# LuMini_1Inch.net
KiCad netlist of a schematic drawn in EAGLE
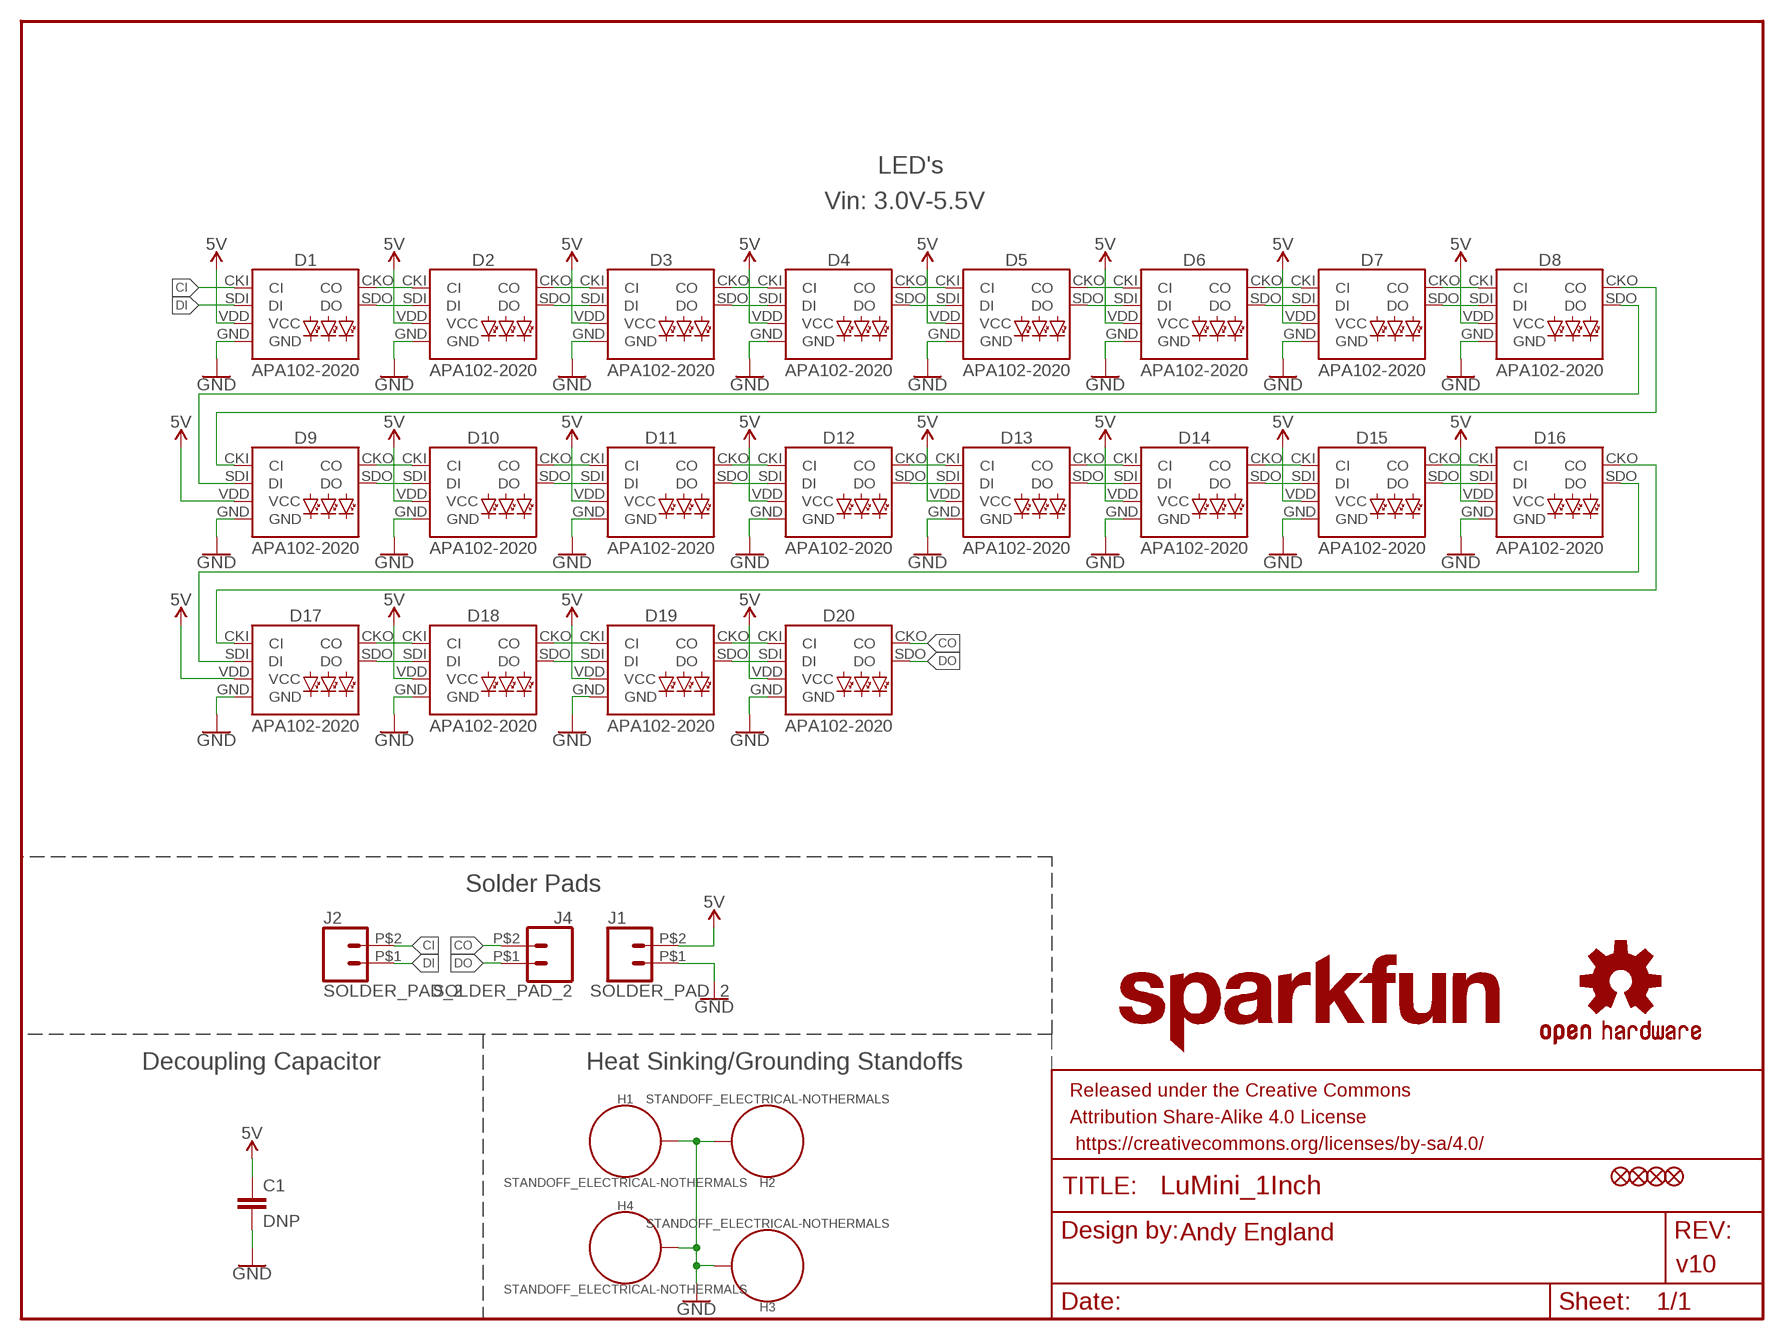
[diagram p0: schematic, sheet 1]

(export (version "E")
  (design (tool "Eeschema 10.0.6"))
  (components
    (comp (ref "C1")
      (value "DNP")
      (footprint "eagle-import:0603")
      (libsource (lib "eagle-import") (part "4.7UF-0603-6.3V-(10%)"))
    )
    (comp (ref "D1")
      (value "APA102-2020")
      (footprint "eagle-import:APA102-2020")
      (libsource (lib "eagle-import") (part "APA102-2020"))
    )
    (comp (ref "D2")
      (value "APA102-2020")
      (footprint "eagle-import:APA102-2020")
      (libsource (lib "eagle-import") (part "APA102-2020"))
    )
    (comp (ref "D3")
      (value "APA102-2020")
      (footprint "eagle-import:APA102-2020")
      (libsource (lib "eagle-import") (part "APA102-2020"))
    )
    (comp (ref "D4")
      (value "APA102-2020")
      (footprint "eagle-import:APA102-2020")
      (libsource (lib "eagle-import") (part "APA102-2020"))
    )
    (comp (ref "D5")
      (value "APA102-2020")
      (footprint "eagle-import:APA102-2020")
      (libsource (lib "eagle-import") (part "APA102-2020"))
    )
    (comp (ref "D6")
      (value "APA102-2020")
      (footprint "eagle-import:APA102-2020")
      (libsource (lib "eagle-import") (part "APA102-2020"))
    )
    (comp (ref "D7")
      (value "APA102-2020")
      (footprint "eagle-import:APA102-2020")
      (libsource (lib "eagle-import") (part "APA102-2020"))
    )
    (comp (ref "D8")
      (value "APA102-2020")
      (footprint "eagle-import:APA102-2020")
      (libsource (lib "eagle-import") (part "APA102-2020"))
    )
    (comp (ref "D9")
      (value "APA102-2020")
      (footprint "eagle-import:APA102-2020")
      (libsource (lib "eagle-import") (part "APA102-2020"))
    )
    (comp (ref "D10")
      (value "APA102-2020")
      (footprint "eagle-import:APA102-2020")
      (libsource (lib "eagle-import") (part "APA102-2020"))
    )
    (comp (ref "D11")
      (value "APA102-2020")
      (footprint "eagle-import:APA102-2020")
      (libsource (lib "eagle-import") (part "APA102-2020"))
    )
    (comp (ref "D12")
      (value "APA102-2020")
      (footprint "eagle-import:APA102-2020")
      (libsource (lib "eagle-import") (part "APA102-2020"))
    )
    (comp (ref "D13")
      (value "APA102-2020")
      (footprint "eagle-import:APA102-2020")
      (libsource (lib "eagle-import") (part "APA102-2020"))
    )
    (comp (ref "D14")
      (value "APA102-2020")
      (footprint "eagle-import:APA102-2020")
      (libsource (lib "eagle-import") (part "APA102-2020"))
    )
    (comp (ref "D15")
      (value "APA102-2020")
      (footprint "eagle-import:APA102-2020")
      (libsource (lib "eagle-import") (part "APA102-2020"))
    )
    (comp (ref "D16")
      (value "APA102-2020")
      (footprint "eagle-import:APA102-2020")
      (libsource (lib "eagle-import") (part "APA102-2020"))
    )
    (comp (ref "D17")
      (value "APA102-2020")
      (footprint "eagle-import:APA102-2020")
      (libsource (lib "eagle-import") (part "APA102-2020"))
    )
    (comp (ref "D18")
      (value "APA102-2020")
      (footprint "eagle-import:APA102-2020")
      (libsource (lib "eagle-import") (part "APA102-2020"))
    )
    (comp (ref "D19")
      (value "APA102-2020")
      (footprint "eagle-import:APA102-2020")
      (libsource (lib "eagle-import") (part "APA102-2020"))
    )
    (comp (ref "D20")
      (value "APA102-2020")
      (footprint "eagle-import:APA102-2020")
      (libsource (lib "eagle-import") (part "APA102-2020"))
    )
    (comp (ref "FD1")
      (value "FIDUCIALUFIDUCIAL")
      (footprint "eagle-import:FIDUCIAL-MICRO")
      (libsource (lib "eagle-import") (part "FIDUCIALUFIDUCIAL"))
    )
    (comp (ref "FD2")
      (value "FIDUCIALUFIDUCIAL")
      (footprint "eagle-import:FIDUCIAL-MICRO")
      (libsource (lib "eagle-import") (part "FIDUCIALUFIDUCIAL"))
    )
    (comp (ref "FD3")
      (value "FIDUCIALUFIDUCIAL")
      (footprint "eagle-import:FIDUCIAL-MICRO")
      (libsource (lib "eagle-import") (part "FIDUCIALUFIDUCIAL"))
    )
    (comp (ref "FD4")
      (value "FIDUCIALUFIDUCIAL")
      (footprint "eagle-import:FIDUCIAL-MICRO")
      (libsource (lib "eagle-import") (part "FIDUCIALUFIDUCIAL"))
    )
    (comp (ref "FRAME1")
      (value "FRAME-LETTER")
      (footprint "eagle-import:CREATIVE_COMMONS")
      (libsource (lib "eagle-import") (part "FRAME-LETTER"))
    )
    (comp (ref "H1")
      (value "STANDOFF_ELECTRICAL-NOTHERMALS")
      (footprint "eagle-import:STANDOFF-ELECTRICAL-NOTHERMALS")
      (libsource (lib "eagle-import") (part "STANDOFF_ELECTRICAL-NOTHERMALS"))
    )
    (comp (ref "H2")
      (value "STANDOFF_ELECTRICAL-NOTHERMALS")
      (footprint "eagle-import:STANDOFF-ELECTRICAL-NOTHERMALS")
      (libsource (lib "eagle-import") (part "STANDOFF_ELECTRICAL-NOTHERMALS"))
    )
    (comp (ref "H3")
      (value "STANDOFF_ELECTRICAL-NOTHERMALS")
      (footprint "eagle-import:STANDOFF-ELECTRICAL-NOTHERMALS")
      (libsource (lib "eagle-import") (part "STANDOFF_ELECTRICAL-NOTHERMALS"))
    )
    (comp (ref "H4")
      (value "STANDOFF_ELECTRICAL-NOTHERMALS")
      (footprint "eagle-import:STANDOFF-ELECTRICAL-NOTHERMALS")
      (libsource (lib "eagle-import") (part "STANDOFF_ELECTRICAL-NOTHERMALS"))
    )
    (comp (ref "J1")
      (value "SOLDER_PAD_2")
      (footprint "eagle-import:SOLDER_PAD_2")
      (libsource (lib "eagle-import") (part "SOLDER_PAD_2"))
    )
    (comp (ref "J2")
      (value "SOLDER_PAD_2")
      (footprint "eagle-import:SOLDER_PAD_2")
      (libsource (lib "eagle-import") (part "SOLDER_PAD_2"))
    )
    (comp (ref "J4")
      (value "SOLDER_PAD_2")
      (footprint "eagle-import:SOLDER_PAD_2")
      (libsource (lib "eagle-import") (part "SOLDER_PAD_2"))
    )
    (comp (ref "LOGO1")
      (value "SFE_LOGO_NAME.1_INCH")
      (footprint "eagle-import:SFE_LOGO_NAME_.1")
      (libsource (lib "eagle-import") (part "SFE_LOGO_NAME.1_INCH"))
    )
    (comp (ref "LOGO2")
      (value "OSHW-LOGOS")
      (footprint "eagle-import:OSHW-LOGO-S")
      (libsource (lib "eagle-import") (part "OSHW-LOGOS"))
    )
  )
  (nets
    (net (code "1") (name "5V") (class "Default")
      (node (ref "C1") (pin "1") (pinfunction "1_1") (pintype "passive"))
      (node (ref "D1") (pin "VDD") (pinfunction "VCC_VDD") (pintype "bidirectional"))
      (node (ref "D10") (pin "VDD") (pinfunction "VCC_VDD") (pintype "bidirectional"))
      (node (ref "D11") (pin "VDD") (pinfunction "VCC_VDD") (pintype "bidirectional"))
      (node (ref "D12") (pin "VDD") (pinfunction "VCC_VDD") (pintype "bidirectional"))
      (node (ref "D13") (pin "VDD") (pinfunction "VCC_VDD") (pintype "bidirectional"))
      (node (ref "D14") (pin "VDD") (pinfunction "VCC_VDD") (pintype "bidirectional"))
      (node (ref "D15") (pin "VDD") (pinfunction "VCC_VDD") (pintype "bidirectional"))
      (node (ref "D16") (pin "VDD") (pinfunction "VCC_VDD") (pintype "bidirectional"))
      (node (ref "D17") (pin "VDD") (pinfunction "VCC_VDD") (pintype "bidirectional"))
      (node (ref "D18") (pin "VDD") (pinfunction "VCC_VDD") (pintype "bidirectional"))
      (node (ref "D19") (pin "VDD") (pinfunction "VCC_VDD") (pintype "bidirectional"))
      (node (ref "D2") (pin "VDD") (pinfunction "VCC_VDD") (pintype "bidirectional"))
      (node (ref "D20") (pin "VDD") (pinfunction "VCC_VDD") (pintype "bidirectional"))
      (node (ref "D3") (pin "VDD") (pinfunction "VCC_VDD") (pintype "bidirectional"))
      (node (ref "D4") (pin "VDD") (pinfunction "VCC_VDD") (pintype "bidirectional"))
      (node (ref "D5") (pin "VDD") (pinfunction "VCC_VDD") (pintype "bidirectional"))
      (node (ref "D6") (pin "VDD") (pinfunction "VCC_VDD") (pintype "bidirectional"))
      (node (ref "D7") (pin "VDD") (pinfunction "VCC_VDD") (pintype "bidirectional"))
      (node (ref "D8") (pin "VDD") (pinfunction "VCC_VDD") (pintype "bidirectional"))
      (node (ref "D9") (pin "VDD") (pinfunction "VCC_VDD") (pintype "bidirectional"))
      (node (ref "J1") (pin "P$2") (pinfunction "2_P$2") (pintype "passive"))
    )
    (net (code "2") (name "CI") (class "Default")
      (node (ref "D1") (pin "CKI") (pinfunction "CI_CKI") (pintype "bidirectional"))
      (node (ref "J2") (pin "P$2") (pinfunction "2_P$2") (pintype "passive"))
    )
    (net (code "3") (name "CO") (class "Default")
      (node (ref "D20") (pin "CKO") (pinfunction "CO_CKO") (pintype "bidirectional"))
      (node (ref "J4") (pin "P$2") (pinfunction "2_P$2") (pintype "passive"))
    )
    (net (code "4") (name "DI") (class "Default")
      (node (ref "D1") (pin "SDI") (pinfunction "DI_SDI") (pintype "bidirectional"))
      (node (ref "J2") (pin "P$1") (pinfunction "1_P$1") (pintype "passive"))
    )
    (net (code "5") (name "DO") (class "Default")
      (node (ref "D20") (pin "SDO") (pinfunction "DO_SDO") (pintype "bidirectional"))
      (node (ref "J4") (pin "P$1") (pinfunction "1_P$1") (pintype "passive"))
    )
    (net (code "6") (name "GND") (class "Default")
      (node (ref "C1") (pin "2") (pinfunction "2_2") (pintype "passive"))
      (node (ref "D1") (pin "GND") (pinfunction "GND_GND") (pintype "bidirectional"))
      (node (ref "D10") (pin "GND") (pinfunction "GND_GND") (pintype "bidirectional"))
      (node (ref "D11") (pin "GND") (pinfunction "GND_GND") (pintype "bidirectional"))
      (node (ref "D12") (pin "GND") (pinfunction "GND_GND") (pintype "bidirectional"))
      (node (ref "D13") (pin "GND") (pinfunction "GND_GND") (pintype "bidirectional"))
      (node (ref "D14") (pin "GND") (pinfunction "GND_GND") (pintype "bidirectional"))
      (node (ref "D15") (pin "GND") (pinfunction "GND_GND") (pintype "bidirectional"))
      (node (ref "D16") (pin "GND") (pinfunction "GND_GND") (pintype "bidirectional"))
      (node (ref "D17") (pin "GND") (pinfunction "GND_GND") (pintype "bidirectional"))
      (node (ref "D18") (pin "GND") (pinfunction "GND_GND") (pintype "bidirectional"))
      (node (ref "D19") (pin "GND") (pinfunction "GND_GND") (pintype "bidirectional"))
      (node (ref "D2") (pin "GND") (pinfunction "GND_GND") (pintype "bidirectional"))
      (node (ref "D20") (pin "GND") (pinfunction "GND_GND") (pintype "bidirectional"))
      (node (ref "D3") (pin "GND") (pinfunction "GND_GND") (pintype "bidirectional"))
      (node (ref "D4") (pin "GND") (pinfunction "GND_GND") (pintype "bidirectional"))
      (node (ref "D5") (pin "GND") (pinfunction "GND_GND") (pintype "bidirectional"))
      (node (ref "D6") (pin "GND") (pinfunction "GND_GND") (pintype "bidirectional"))
      (node (ref "D7") (pin "GND") (pinfunction "GND_GND") (pintype "bidirectional"))
      (node (ref "D8") (pin "GND") (pinfunction "GND_GND") (pintype "bidirectional"))
      (node (ref "D9") (pin "GND") (pinfunction "GND_GND") (pintype "bidirectional"))
      (node (ref "H1") (pin "P1") (pinfunction "P$1_P1") (pintype "bidirectional"))
      (node (ref "H2") (pin "P1") (pinfunction "P$1_P1") (pintype "bidirectional"))
      (node (ref "H3") (pin "P1") (pinfunction "P$1_P1") (pintype "bidirectional"))
      (node (ref "H4") (pin "P1") (pinfunction "P$1_P1") (pintype "bidirectional"))
      (node (ref "J1") (pin "P$1") (pinfunction "1_P$1") (pintype "passive"))
    )
    (net (code "7") (name "Net-(D1-CO)") (class "Default")
      (node (ref "D1") (pin "CKO") (pinfunction "CO_CKO") (pintype "bidirectional"))
      (node (ref "D2") (pin "CKI") (pinfunction "CI_CKI") (pintype "bidirectional"))
    )
    (net (code "8") (name "Net-(D1-DO)") (class "Default")
      (node (ref "D1") (pin "SDO") (pinfunction "DO_SDO") (pintype "bidirectional"))
      (node (ref "D2") (pin "SDI") (pinfunction "DI_SDI") (pintype "bidirectional"))
    )
    (net (code "9") (name "Net-(D2-CO)") (class "Default")
      (node (ref "D2") (pin "CKO") (pinfunction "CO_CKO") (pintype "bidirectional"))
      (node (ref "D3") (pin "CKI") (pinfunction "CI_CKI") (pintype "bidirectional"))
    )
    (net (code "10") (name "Net-(D2-DO)") (class "Default")
      (node (ref "D2") (pin "SDO") (pinfunction "DO_SDO") (pintype "bidirectional"))
      (node (ref "D3") (pin "SDI") (pinfunction "DI_SDI") (pintype "bidirectional"))
    )
    (net (code "11") (name "Net-(D3-CO)") (class "Default")
      (node (ref "D3") (pin "CKO") (pinfunction "CO_CKO") (pintype "bidirectional"))
      (node (ref "D4") (pin "CKI") (pinfunction "CI_CKI") (pintype "bidirectional"))
    )
    (net (code "12") (name "Net-(D3-DO)") (class "Default")
      (node (ref "D3") (pin "SDO") (pinfunction "DO_SDO") (pintype "bidirectional"))
      (node (ref "D4") (pin "SDI") (pinfunction "DI_SDI") (pintype "bidirectional"))
    )
    (net (code "13") (name "Net-(D4-CO)") (class "Default")
      (node (ref "D4") (pin "CKO") (pinfunction "CO_CKO") (pintype "bidirectional"))
      (node (ref "D5") (pin "CKI") (pinfunction "CI_CKI") (pintype "bidirectional"))
    )
    (net (code "14") (name "Net-(D4-DO)") (class "Default")
      (node (ref "D4") (pin "SDO") (pinfunction "DO_SDO") (pintype "bidirectional"))
      (node (ref "D5") (pin "SDI") (pinfunction "DI_SDI") (pintype "bidirectional"))
    )
    (net (code "15") (name "Net-(D5-CO)") (class "Default")
      (node (ref "D5") (pin "CKO") (pinfunction "CO_CKO") (pintype "bidirectional"))
      (node (ref "D6") (pin "CKI") (pinfunction "CI_CKI") (pintype "bidirectional"))
    )
    (net (code "16") (name "Net-(D5-DO)") (class "Default")
      (node (ref "D5") (pin "SDO") (pinfunction "DO_SDO") (pintype "bidirectional"))
      (node (ref "D6") (pin "SDI") (pinfunction "DI_SDI") (pintype "bidirectional"))
    )
    (net (code "17") (name "Net-(D6-CO)") (class "Default")
      (node (ref "D6") (pin "CKO") (pinfunction "CO_CKO") (pintype "bidirectional"))
      (node (ref "D7") (pin "CKI") (pinfunction "CI_CKI") (pintype "bidirectional"))
    )
    (net (code "18") (name "Net-(D6-DO)") (class "Default")
      (node (ref "D6") (pin "SDO") (pinfunction "DO_SDO") (pintype "bidirectional"))
      (node (ref "D7") (pin "SDI") (pinfunction "DI_SDI") (pintype "bidirectional"))
    )
    (net (code "19") (name "Net-(D7-CO)") (class "Default")
      (node (ref "D7") (pin "CKO") (pinfunction "CO_CKO") (pintype "bidirectional"))
      (node (ref "D8") (pin "CKI") (pinfunction "CI_CKI") (pintype "bidirectional"))
    )
    (net (code "20") (name "Net-(D7-DO)") (class "Default")
      (node (ref "D7") (pin "SDO") (pinfunction "DO_SDO") (pintype "bidirectional"))
      (node (ref "D8") (pin "SDI") (pinfunction "DI_SDI") (pintype "bidirectional"))
    )
    (net (code "21") (name "Net-(D8-CO)") (class "Default")
      (node (ref "D8") (pin "CKO") (pinfunction "CO_CKO") (pintype "bidirectional"))
      (node (ref "D9") (pin "CKI") (pinfunction "CI_CKI") (pintype "bidirectional"))
    )
    (net (code "22") (name "Net-(D8-DO)") (class "Default")
      (node (ref "D8") (pin "SDO") (pinfunction "DO_SDO") (pintype "bidirectional"))
      (node (ref "D9") (pin "SDI") (pinfunction "DI_SDI") (pintype "bidirectional"))
    )
    (net (code "23") (name "Net-(D10-CI)") (class "Default")
      (node (ref "D10") (pin "CKI") (pinfunction "CI_CKI") (pintype "bidirectional"))
      (node (ref "D9") (pin "CKO") (pinfunction "CO_CKO") (pintype "bidirectional"))
    )
    (net (code "24") (name "Net-(D10-CO)") (class "Default")
      (node (ref "D10") (pin "CKO") (pinfunction "CO_CKO") (pintype "bidirectional"))
      (node (ref "D11") (pin "CKI") (pinfunction "CI_CKI") (pintype "bidirectional"))
    )
    (net (code "25") (name "Net-(D10-DI)") (class "Default")
      (node (ref "D10") (pin "SDI") (pinfunction "DI_SDI") (pintype "bidirectional"))
      (node (ref "D9") (pin "SDO") (pinfunction "DO_SDO") (pintype "bidirectional"))
    )
    (net (code "26") (name "Net-(D10-DO)") (class "Default")
      (node (ref "D10") (pin "SDO") (pinfunction "DO_SDO") (pintype "bidirectional"))
      (node (ref "D11") (pin "SDI") (pinfunction "DI_SDI") (pintype "bidirectional"))
    )
    (net (code "27") (name "Net-(D11-CO)") (class "Default")
      (node (ref "D11") (pin "CKO") (pinfunction "CO_CKO") (pintype "bidirectional"))
      (node (ref "D12") (pin "CKI") (pinfunction "CI_CKI") (pintype "bidirectional"))
    )
    (net (code "28") (name "Net-(D11-DO)") (class "Default")
      (node (ref "D11") (pin "SDO") (pinfunction "DO_SDO") (pintype "bidirectional"))
      (node (ref "D12") (pin "SDI") (pinfunction "DI_SDI") (pintype "bidirectional"))
    )
    (net (code "29") (name "Net-(D12-CO)") (class "Default")
      (node (ref "D12") (pin "CKO") (pinfunction "CO_CKO") (pintype "bidirectional"))
      (node (ref "D13") (pin "CKI") (pinfunction "CI_CKI") (pintype "bidirectional"))
    )
    (net (code "30") (name "Net-(D12-DO)") (class "Default")
      (node (ref "D12") (pin "SDO") (pinfunction "DO_SDO") (pintype "bidirectional"))
      (node (ref "D13") (pin "SDI") (pinfunction "DI_SDI") (pintype "bidirectional"))
    )
    (net (code "31") (name "Net-(D13-CO)") (class "Default")
      (node (ref "D13") (pin "CKO") (pinfunction "CO_CKO") (pintype "bidirectional"))
      (node (ref "D14") (pin "CKI") (pinfunction "CI_CKI") (pintype "bidirectional"))
    )
    (net (code "32") (name "Net-(D13-DO)") (class "Default")
      (node (ref "D13") (pin "SDO") (pinfunction "DO_SDO") (pintype "bidirectional"))
      (node (ref "D14") (pin "SDI") (pinfunction "DI_SDI") (pintype "bidirectional"))
    )
    (net (code "33") (name "Net-(D14-CO)") (class "Default")
      (node (ref "D14") (pin "CKO") (pinfunction "CO_CKO") (pintype "bidirectional"))
      (node (ref "D15") (pin "CKI") (pinfunction "CI_CKI") (pintype "bidirectional"))
    )
    (net (code "34") (name "Net-(D14-DO)") (class "Default")
      (node (ref "D14") (pin "SDO") (pinfunction "DO_SDO") (pintype "bidirectional"))
      (node (ref "D15") (pin "SDI") (pinfunction "DI_SDI") (pintype "bidirectional"))
    )
    (net (code "35") (name "Net-(D15-CO)") (class "Default")
      (node (ref "D15") (pin "CKO") (pinfunction "CO_CKO") (pintype "bidirectional"))
      (node (ref "D16") (pin "CKI") (pinfunction "CI_CKI") (pintype "bidirectional"))
    )
    (net (code "36") (name "Net-(D15-DO)") (class "Default")
      (node (ref "D15") (pin "SDO") (pinfunction "DO_SDO") (pintype "bidirectional"))
      (node (ref "D16") (pin "SDI") (pinfunction "DI_SDI") (pintype "bidirectional"))
    )
    (net (code "37") (name "Net-(D16-CO)") (class "Default")
      (node (ref "D16") (pin "CKO") (pinfunction "CO_CKO") (pintype "bidirectional"))
      (node (ref "D17") (pin "CKI") (pinfunction "CI_CKI") (pintype "bidirectional"))
    )
    (net (code "38") (name "Net-(D16-DO)") (class "Default")
      (node (ref "D16") (pin "SDO") (pinfunction "DO_SDO") (pintype "bidirectional"))
      (node (ref "D17") (pin "SDI") (pinfunction "DI_SDI") (pintype "bidirectional"))
    )
    (net (code "39") (name "Net-(D17-CO)") (class "Default")
      (node (ref "D17") (pin "CKO") (pinfunction "CO_CKO") (pintype "bidirectional"))
      (node (ref "D18") (pin "CKI") (pinfunction "CI_CKI") (pintype "bidirectional"))
    )
    (net (code "40") (name "Net-(D17-DO)") (class "Default")
      (node (ref "D17") (pin "SDO") (pinfunction "DO_SDO") (pintype "bidirectional"))
      (node (ref "D18") (pin "SDI") (pinfunction "DI_SDI") (pintype "bidirectional"))
    )
    (net (code "41") (name "Net-(D18-CO)") (class "Default")
      (node (ref "D18") (pin "CKO") (pinfunction "CO_CKO") (pintype "bidirectional"))
      (node (ref "D19") (pin "CKI") (pinfunction "CI_CKI") (pintype "bidirectional"))
    )
    (net (code "42") (name "Net-(D18-DO)") (class "Default")
      (node (ref "D18") (pin "SDO") (pinfunction "DO_SDO") (pintype "bidirectional"))
      (node (ref "D19") (pin "SDI") (pinfunction "DI_SDI") (pintype "bidirectional"))
    )
    (net (code "43") (name "Net-(D19-CO)") (class "Default")
      (node (ref "D19") (pin "CKO") (pinfunction "CO_CKO") (pintype "bidirectional"))
      (node (ref "D20") (pin "CKI") (pinfunction "CI_CKI") (pintype "bidirectional"))
    )
    (net (code "44") (name "Net-(D19-DO)") (class "Default")
      (node (ref "D19") (pin "SDO") (pinfunction "DO_SDO") (pintype "bidirectional"))
      (node (ref "D20") (pin "SDI") (pinfunction "DI_SDI") (pintype "bidirectional"))
    )
  )
)
